# mainboard_interface_v1_3.net
KiCad netlist of a schematic drawn in Altium Designer
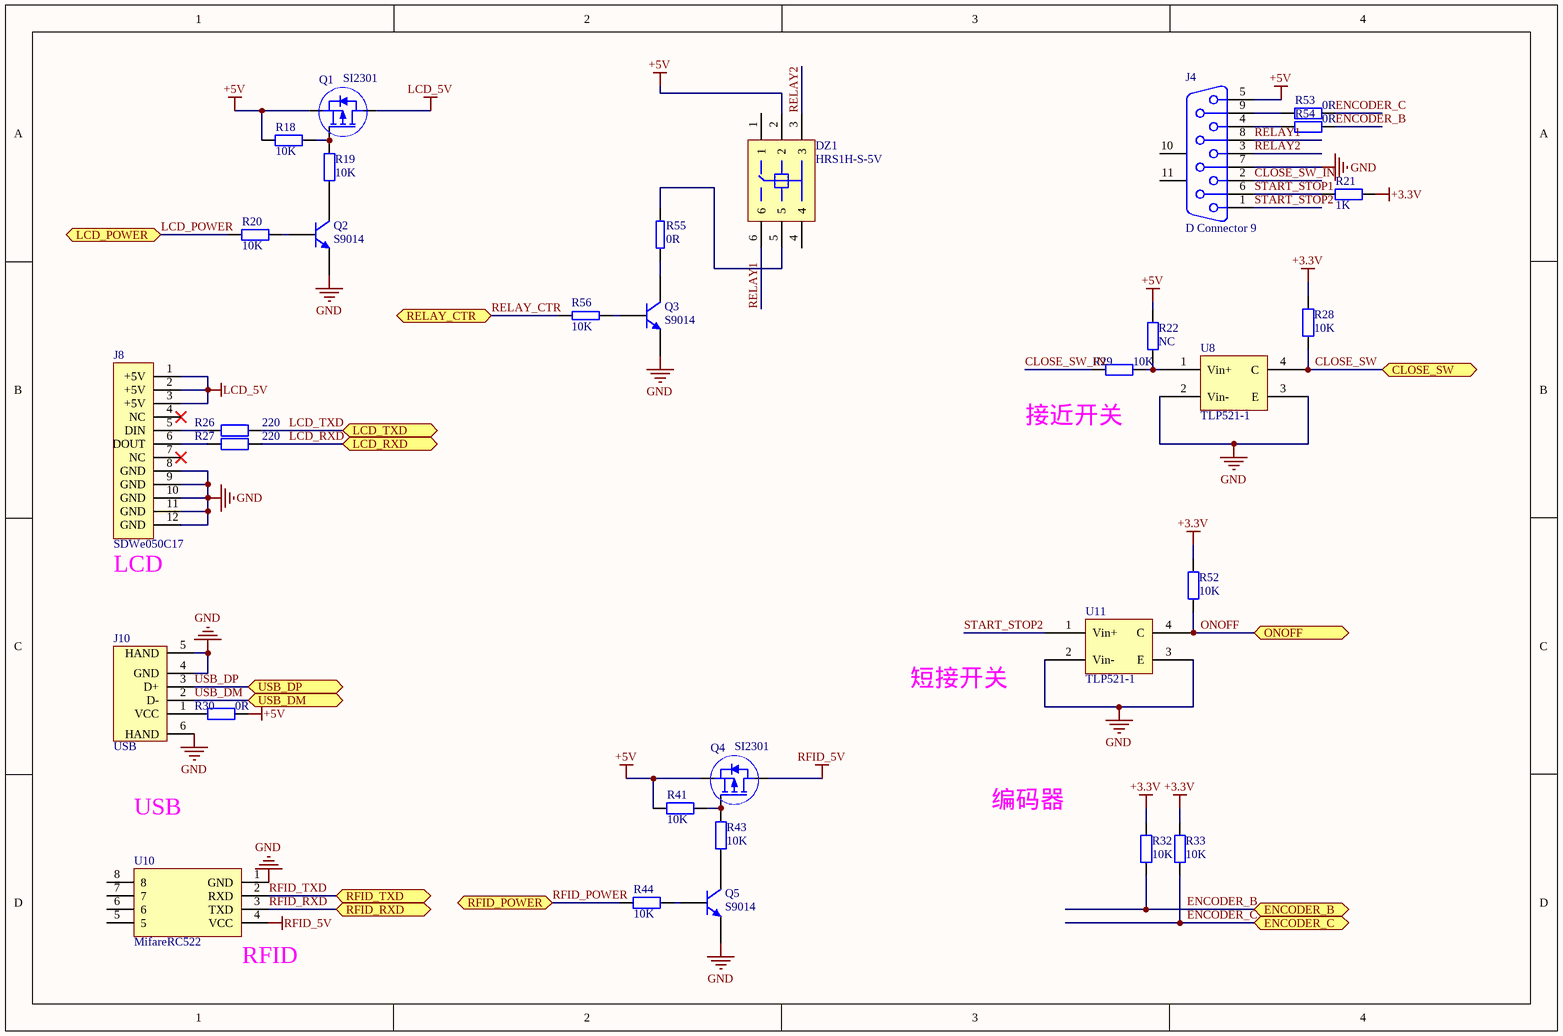
[diagram p0: mainboard_interface.v1.3.SchDoc]

(export (version "E")
  (design (tool "Eeschema 10.0.6"))
  (components
    (comp (ref "DZ1") (value "HRS1H-S-5V") (libsource (lib "Componet") (part "HRS1H-S-5V")))
    (comp (ref "J4")
      (value "D Connector 9")
      (footprint "DSUB1.385-2H9")
      (description "Receptacle Assembly, 9 Position, Right Angle")
      (fields (field (name "PUBLISHER") "Altium Limited"))
      (libsource (lib "Miscellaneous Connectors") (part "D Connector 9"))
    )
    (comp (ref "J8")
      (value "SDWe050C17")
      (footprint "FCC1.0-10")
      (libsource (lib "Connector") (part "SH-12"))
    )
    (comp (ref "J10") (value "USB") (footprint "USB_FEMALE_A") (libsource (lib "Connector") (part "USB")))
    (comp (ref "Q1") (value "SI2301") (footprint "MOS-N_SOT-23") (libsource (lib "*") (part "MOS-P_SOT-23")))
    (comp (ref "Q2") (value "S9014") (footprint "901X_SOT-23") (libsource (lib "Componet") (part "NPN")))
    (comp (ref "Q3") (value "S9014") (footprint "901X_SOT-23") (libsource (lib "Componet") (part "NPN")))
    (comp (ref "Q4") (value "SI2301") (footprint "MOS-N_SOT-23") (libsource (lib "*") (part "MOS-P_SOT-23")))
    (comp (ref "Q5") (value "S9014") (footprint "901X_SOT-23") (libsource (lib "Componet") (part "NPN")))
    (comp (ref "R18")
      (value "10K")
      (footprint "0805")
      (description "Resistor")
      (fields (field (name "PUBLISHER") "Altium Limited"))
      (libsource (lib "") (part "Res2_2"))
    )
    (comp (ref "R19")
      (value "10K")
      (footprint "0805")
      (description "Resistor")
      (fields (field (name "PUBLISHER") "Altium Limited"))
      (libsource (lib "") (part "Res2_1"))
    )
    (comp (ref "R20")
      (value "10K")
      (footprint "0805")
      (description "Resistor")
      (fields (field (name "PUBLISHER") "Altium Limited"))
      (libsource (lib "") (part "Res2_2"))
    )
    (comp (ref "R21")
      (value "1K")
      (footprint "0805")
      (description "Resistor")
      (fields (field (name "PUBLISHER") "Altium Limited"))
      (libsource (lib "") (part "Res2_2"))
    )
    (comp (ref "R22")
      (value "NC")
      (footprint "0805")
      (description "Resistor")
      (fields (field (name "PUBLISHER") "Altium Limited"))
      (libsource (lib "TIAN's Schlib") (part "Res2"))
    )
    (comp (ref "R26")
      (value "220")
      (footprint "0805")
      (description "Resistor")
      (fields (field (name "PUBLISHER") "Altium Limited"))
      (libsource (lib "") (part "Res2_2"))
    )
    (comp (ref "R27")
      (value "220")
      (footprint "0805")
      (description "Resistor")
      (fields (field (name "PUBLISHER") "Altium Limited"))
      (libsource (lib "") (part "Res2_2"))
    )
    (comp (ref "R28")
      (value "10K")
      (footprint "0805")
      (description "Resistor")
      (fields (field (name "PUBLISHER") "Altium Limited"))
      (libsource (lib "TIAN's Schlib") (part "Res2"))
    )
    (comp (ref "R29")
      (value "10K")
      (footprint "0805")
      (description "Resistor")
      (fields (field (name "PUBLISHER") "Altium Limited"))
      (libsource (lib "") (part "Res2_3"))
    )
    (comp (ref "R30")
      (value "0R")
      (footprint "0805")
      (description "Resistor")
      (fields (field (name "PUBLISHER") "Altium Limited"))
      (libsource (lib "") (part "Res2_3"))
    )
    (comp (ref "R32")
      (value "10K")
      (footprint "0805")
      (description "Resistor")
      (fields (field (name "PUBLISHER") "Altium Limited"))
      (libsource (lib "TIAN's Schlib") (part "Res2"))
    )
    (comp (ref "R33")
      (value "10K")
      (footprint "0805")
      (description "Resistor")
      (fields (field (name "PUBLISHER") "Altium Limited"))
      (libsource (lib "TIAN's Schlib") (part "Res2"))
    )
    (comp (ref "R41")
      (value "10K")
      (footprint "0805")
      (description "Resistor")
      (fields (field (name "PUBLISHER") "Altium Limited"))
      (libsource (lib "") (part "Res2_2"))
    )
    (comp (ref "R43")
      (value "10K")
      (footprint "0805")
      (description "Resistor")
      (fields (field (name "PUBLISHER") "Altium Limited"))
      (libsource (lib "") (part "Res2_1"))
    )
    (comp (ref "R44")
      (value "10K")
      (footprint "0805")
      (description "Resistor")
      (fields (field (name "PUBLISHER") "Altium Limited"))
      (libsource (lib "") (part "Res2_2"))
    )
    (comp (ref "R52")
      (value "10K")
      (footprint "0805")
      (description "Resistor")
      (fields (field (name "PUBLISHER") "Altium Limited"))
      (libsource (lib "TIAN's Schlib") (part "Res2"))
    )
    (comp (ref "R53")
      (value "0R")
      (footprint "0805")
      (description "Resistor")
      (fields (field (name "PUBLISHER") "Altium Limited"))
      (libsource (lib "") (part "Res2_2"))
    )
    (comp (ref "R54")
      (value "0R")
      (footprint "0805")
      (description "Resistor")
      (fields (field (name "PUBLISHER") "Altium Limited"))
      (libsource (lib "") (part "Res2_2"))
    )
    (comp (ref "R55")
      (value "0R")
      (footprint "0805")
      (description "电阻")
      (libsource (lib "Component") (part "RES"))
    )
    (comp (ref "R56")
      (value "10K")
      (footprint "0805")
      (description "电阻")
      (libsource (lib "Component") (part "RES"))
    )
    (comp (ref "U8") (value "TLP521-1") (footprint "TLP521-1") (libsource (lib "Chip") (part "TLP521-1")))
    (comp (ref "U10")
      (value "MifareRC522")
      (footprint "MifareRC522")
      (libsource (lib "Componet") (part "MifareRC522"))
    )
    (comp (ref "U11") (value "TLP521-1") (footprint "TLP521-1") (libsource (lib "Chip") (part "TLP521-1")))
  )
  (nets
    (net (code "1") (name "+3.3V") (class "Default")
      (node (ref "R21") (pin "2") (pinfunction "2_2") (pintype "passive"))
      (node (ref "R28") (pin "1") (pinfunction "1_1") (pintype "passive"))
      (node (ref "R32") (pin "1") (pinfunction "1_1") (pintype "passive"))
      (node (ref "R33") (pin "1") (pinfunction "1_1") (pintype "passive"))
      (node (ref "R52") (pin "1") (pinfunction "1_1") (pintype "passive"))
    )
    (net (code "2") (name "+5V") (class "Default")
      (node (ref "DZ1") (pin "2") (pinfunction "2_2") (pintype "passive"))
      (node (ref "J4") (pin "5") (pinfunction "5_5") (pintype "passive"))
      (node (ref "Q1") (pin "S") (pinfunction "S_S") (pintype "passive"))
      (node (ref "Q4") (pin "S") (pinfunction "S_S") (pintype "passive"))
      (node (ref "R18") (pin "1") (pinfunction "1_1") (pintype "passive"))
      (node (ref "R22") (pin "1") (pinfunction "1_1") (pintype "passive"))
      (node (ref "R30") (pin "1") (pinfunction "1_1") (pintype "passive"))
      (node (ref "R41") (pin "1") (pinfunction "1_1") (pintype "passive"))
    )
    (net (code "3") (name "/CLOSE_SW") (class "Default")
      (node (ref "R28") (pin "2") (pinfunction "2_2") (pintype "passive"))
      (node (ref "U8") (pin "4") (pinfunction "C_4") (pintype "passive"))
    )
    (net (code "4") (name "/CLOSE_SW_IN") (class "Default")
      (node (ref "J4") (pin "2") (pinfunction "2_2") (pintype "passive"))
      (node (ref "R29") (pin "2") (pinfunction "2_2") (pintype "passive"))
    )
    (net (code "5") (name "/ENCODER_B") (class "Default")
      (node (ref "R32") (pin "2") (pinfunction "2_2") (pintype "passive"))
      (node (ref "R54") (pin "2") (pinfunction "2_2") (pintype "passive"))
    )
    (net (code "6") (name "/ENCODER_C") (class "Default")
      (node (ref "R33") (pin "2") (pinfunction "2_2") (pintype "passive"))
      (node (ref "R53") (pin "2") (pinfunction "2_2") (pintype "passive"))
    )
    (net (code "7") (name "/LCD_POWER") (class "Default")
      (node (ref "R20") (pin "1") (pinfunction "1_1") (pintype "passive"))
    )
    (net (code "8") (name "/LCD_RXD") (class "Default")
      (node (ref "R27") (pin "2") (pinfunction "2_2") (pintype "passive"))
    )
    (net (code "9") (name "/LCD_TXD") (class "Default")
      (node (ref "R26") (pin "2") (pinfunction "2_2") (pintype "passive"))
    )
    (net (code "10") (name "/ONOFF") (class "Default")
      (node (ref "R52") (pin "2") (pinfunction "2_2") (pintype "passive"))
      (node (ref "U11") (pin "4") (pinfunction "C_4") (pintype "passive"))
    )
    (net (code "11") (name "/RELAY1") (class "Default")
      (node (ref "DZ1") (pin "6") (pinfunction "6_6") (pintype "passive"))
      (node (ref "J4") (pin "8") (pinfunction "8_8") (pintype "passive"))
    )
    (net (code "12") (name "/RELAY2") (class "Default")
      (node (ref "DZ1") (pin "3") (pinfunction "3_3") (pintype "passive"))
      (node (ref "J4") (pin "3") (pinfunction "3_3") (pintype "passive"))
    )
    (net (code "13") (name "/RELAY_CTR") (class "Default")
      (node (ref "R56") (pin "2") (pinfunction "2_2") (pintype "passive"))
    )
    (net (code "14") (name "/RFID_POWER") (class "Default")
      (node (ref "R44") (pin "1") (pinfunction "1_1") (pintype "passive"))
    )
    (net (code "15") (name "/RFID_RXD") (class "Default")
      (node (ref "U10") (pin "3") (pinfunction "TXD_3") (pintype "passive"))
    )
    (net (code "16") (name "/RFID_TXD") (class "Default")
      (node (ref "U10") (pin "2") (pinfunction "RXD_2") (pintype "passive"))
    )
    (net (code "17") (name "/START_STOP1") (class "Default")
      (node (ref "J4") (pin "6") (pinfunction "6_6") (pintype "passive"))
      (node (ref "R21") (pin "1") (pinfunction "1_1") (pintype "passive"))
    )
    (net (code "18") (name "/START_STOP2") (class "Default")
      (node (ref "J4") (pin "1") (pinfunction "1_1") (pintype "passive"))
      (node (ref "U11") (pin "1") (pinfunction "Vin+_1") (pintype "passive"))
    )
    (net (code "19") (name "/USB_DM") (class "Default")
      (node (ref "J10") (pin "2") (pinfunction "D-_2") (pintype "passive"))
    )
    (net (code "20") (name "/USB_DP") (class "Default")
      (node (ref "J10") (pin "3") (pinfunction "D+_3") (pintype "passive"))
    )
    (net (code "21") (name "GND") (class "Default")
      (node (ref "J10") (pin "4") (pinfunction "GND_4") (pintype "passive"))
      (node (ref "J10") (pin "5") (pinfunction "HAND_5") (pintype "passive"))
      (node (ref "J10") (pin "6") (pinfunction "HAND_6") (pintype "passive"))
      (node (ref "J4") (pin "7") (pinfunction "7_7") (pintype "passive"))
      (node (ref "J8") (pin "10") (pinfunction "GND_10") (pintype "passive"))
      (node (ref "J8") (pin "11") (pinfunction "GND_11") (pintype "passive"))
      (node (ref "J8") (pin "12") (pinfunction "GND_12") (pintype "passive"))
      (node (ref "J8") (pin "8") (pinfunction "GND_8") (pintype "passive"))
      (node (ref "J8") (pin "9") (pinfunction "GND_9") (pintype "passive"))
      (node (ref "Q2") (pin "3") (pinfunction "E_3") (pintype "passive"))
      (node (ref "Q3") (pin "3") (pinfunction "E_3") (pintype "passive"))
      (node (ref "Q5") (pin "3") (pinfunction "E_3") (pintype "passive"))
      (node (ref "U10") (pin "1") (pinfunction "GND_1") (pintype "passive"))
      (node (ref "U11") (pin "2") (pinfunction "Vin-_2") (pintype "passive"))
      (node (ref "U11") (pin "3") (pinfunction "E_3") (pintype "passive"))
      (node (ref "U8") (pin "2") (pinfunction "Vin-_2") (pintype "passive"))
      (node (ref "U8") (pin "3") (pinfunction "E_3") (pintype "passive"))
    )
    (net (code "22") (name "LCD_5V") (class "Default")
      (node (ref "J8") (pin "1") (pinfunction "+5V_1") (pintype "passive"))
      (node (ref "J8") (pin "2") (pinfunction "+5V_2") (pintype "passive"))
      (node (ref "J8") (pin "3") (pinfunction "+5V_3") (pintype "passive"))
      (node (ref "Q1") (pin "D") (pinfunction "D_D") (pintype "passive"))
    )
    (net (code "23") (name "Net-(DZ1-Pad5)") (class "Default")
      (node (ref "DZ1") (pin "5") (pinfunction "5_5") (pintype "passive"))
      (node (ref "R55") (pin "2") (pinfunction "2_2") (pintype "passive"))
    )
    (net (code "24") (name "Net-(J4-Pad4)") (class "Default")
      (node (ref "J4") (pin "4") (pinfunction "4_4") (pintype "passive"))
      (node (ref "R54") (pin "1") (pinfunction "1_1") (pintype "passive"))
    )
    (net (code "25") (name "Net-(J4-Pad9)") (class "Default")
      (node (ref "J4") (pin "9") (pinfunction "9_9") (pintype "passive"))
      (node (ref "R53") (pin "1") (pinfunction "1_1") (pintype "passive"))
    )
    (net (code "26") (name "Net-(J8-DIN)") (class "Default")
      (node (ref "J8") (pin "5") (pinfunction "DIN_5") (pintype "passive"))
      (node (ref "R26") (pin "1") (pinfunction "1_1") (pintype "passive"))
    )
    (net (code "27") (name "Net-(J8-DOUT)") (class "Default")
      (node (ref "J8") (pin "6") (pinfunction "DOUT_6") (pintype "passive"))
      (node (ref "R27") (pin "1") (pinfunction "1_1") (pintype "passive"))
    )
    (net (code "28") (name "Net-(J10-VCC)") (class "Default")
      (node (ref "J10") (pin "1") (pinfunction "VCC_1") (pintype "passive"))
      (node (ref "R30") (pin "2") (pinfunction "2_2") (pintype "passive"))
    )
    (net (code "29") (name "Net-(Q1-PadG)") (class "Default")
      (node (ref "Q1") (pin "G") (pinfunction "G_G") (pintype "passive"))
      (node (ref "R18") (pin "2") (pinfunction "2_2") (pintype "passive"))
      (node (ref "R19") (pin "2") (pinfunction "2_2") (pintype "passive"))
    )
    (net (code "30") (name "Net-(Q2-B)") (class "Default")
      (node (ref "Q2") (pin "2") (pinfunction "B_2") (pintype "passive"))
      (node (ref "R20") (pin "2") (pinfunction "2_2") (pintype "passive"))
    )
    (net (code "31") (name "Net-(Q2-C)") (class "Default")
      (node (ref "Q2") (pin "1") (pinfunction "C_1") (pintype "passive"))
      (node (ref "R19") (pin "1") (pinfunction "1_1") (pintype "passive"))
    )
    (net (code "32") (name "Net-(Q3-B)") (class "Default")
      (node (ref "Q3") (pin "2") (pinfunction "B_2") (pintype "passive"))
      (node (ref "R56") (pin "1") (pinfunction "1_1") (pintype "passive"))
    )
    (net (code "33") (name "Net-(Q3-C)") (class "Default")
      (node (ref "Q3") (pin "1") (pinfunction "C_1") (pintype "passive"))
      (node (ref "R55") (pin "1") (pinfunction "1_1") (pintype "passive"))
    )
    (net (code "34") (name "Net-(Q4-PadG)") (class "Default")
      (node (ref "Q4") (pin "G") (pinfunction "G_G") (pintype "passive"))
      (node (ref "R41") (pin "2") (pinfunction "2_2") (pintype "passive"))
      (node (ref "R43") (pin "2") (pinfunction "2_2") (pintype "passive"))
    )
    (net (code "35") (name "Net-(Q5-B)") (class "Default")
      (node (ref "Q5") (pin "2") (pinfunction "B_2") (pintype "passive"))
      (node (ref "R44") (pin "2") (pinfunction "2_2") (pintype "passive"))
    )
    (net (code "36") (name "Net-(Q5-C)") (class "Default")
      (node (ref "Q5") (pin "1") (pinfunction "C_1") (pintype "passive"))
      (node (ref "R43") (pin "1") (pinfunction "1_1") (pintype "passive"))
    )
    (net (code "37") (name "Net-(U8-Vin+)") (class "Default")
      (node (ref "R22") (pin "2") (pinfunction "2_2") (pintype "passive"))
      (node (ref "R29") (pin "1") (pinfunction "1_1") (pintype "passive"))
      (node (ref "U8") (pin "1") (pinfunction "Vin+_1") (pintype "passive"))
    )
    (net (code "38") (name "RFID_5V") (class "Default")
      (node (ref "Q4") (pin "D") (pinfunction "D_D") (pintype "passive"))
      (node (ref "U10") (pin "4") (pinfunction "VCC_4") (pintype "passive"))
    )
    (net (code "39") (name "unconnected-(DZ1-Pad1)") (class "Default")
      (node (ref "DZ1") (pin "1") (pinfunction "1_1") (pintype "passive"))
    )
    (net (code "40") (name "unconnected-(DZ1-Pad4)") (class "Default")
      (node (ref "DZ1") (pin "4") (pinfunction "4_4") (pintype "passive"))
    )
    (net (code "41") (name "unconnected-(J4-MH1-Pad10)") (class "Default")
      (node (ref "J4") (pin "10") (pinfunction "MH1_10") (pintype "passive"))
    )
    (net (code "42") (name "unconnected-(J4-MH2-Pad11)") (class "Default")
      (node (ref "J4") (pin "11") (pinfunction "MH2_11") (pintype "passive"))
    )
    (net (code "43") (name "unconnected-(J8-NC-Pad4)") (class "Default")
      (node (ref "J8") (pin "4") (pinfunction "NC_4") (pintype "passive+no_connect"))
    )
    (net (code "44") (name "unconnected-(J8-NC-Pad7)") (class "Default")
      (node (ref "J8") (pin "7") (pinfunction "NC_7") (pintype "passive+no_connect"))
    )
    (net (code "45") (name "unconnected-(U10-Pad5)") (class "Default")
      (node (ref "U10") (pin "5") (pinfunction "5_5") (pintype "passive"))
    )
    (net (code "46") (name "unconnected-(U10-Pad6)") (class "Default")
      (node (ref "U10") (pin "6") (pinfunction "6_6") (pintype "passive"))
    )
    (net (code "47") (name "unconnected-(U10-Pad7)") (class "Default")
      (node (ref "U10") (pin "7") (pinfunction "7_7") (pintype "passive"))
    )
    (net (code "48") (name "unconnected-(U10-Pad8)") (class "Default")
      (node (ref "U10") (pin "8") (pinfunction "8_8") (pintype "passive"))
    )
  )
)
